# 555-Synth.net
KiCad netlist of a schematic drawn in EAGLE
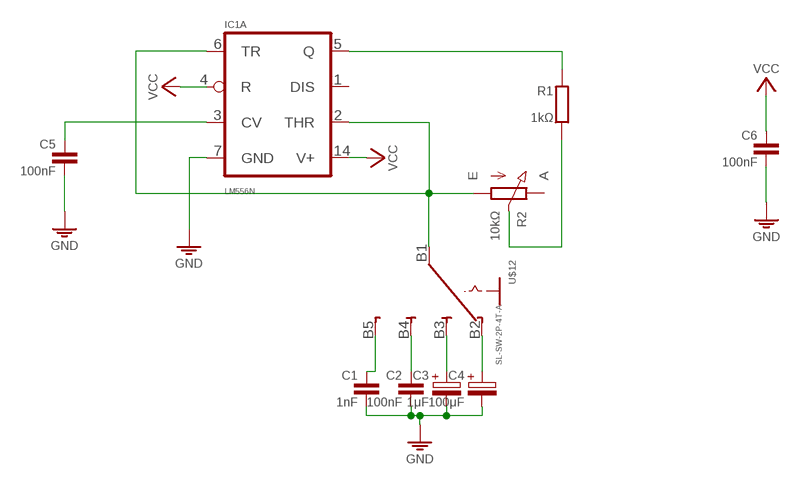
[diagram p0: schematic, sheet 1]

(export (version "E")
  (design (tool "Eeschema 10.0.6"))
  (components
    (comp (ref "C1")
      (value "1nF")
      (footprint "eagle-import:C050-020X044_V")
      (libsource (lib "eagle-import") (part "C050-020X044/V"))
    )
    (comp (ref "C2")
      (value "100nF")
      (footprint "eagle-import:C050-020X044_V")
      (libsource (lib "eagle-import") (part "C050-020X044/V"))
    )
    (comp (ref "C3")
      (value "1μF")
      (footprint "eagle-import:E2,5-5_V")
      (libsource (lib "eagle-import") (part "CPOLE2,5-5/V"))
    )
    (comp (ref "C4")
      (value "100μF")
      (footprint "eagle-import:E2,5-5_V")
      (libsource (lib "eagle-import") (part "CPOLE2,5-5/V"))
    )
    (comp (ref "C5")
      (value "100nF")
      (footprint "eagle-import:C050-020X044_V")
      (libsource (lib "eagle-import") (part "C050-020X044/V"))
    )
    (comp (ref "C6")
      (value "100nF")
      (footprint "eagle-import:C050-020X044_V")
      (libsource (lib "eagle-import") (part "C050-020X044/V"))
    )
    (comp (ref "IC1")
      (value "LM556N")
      (footprint "eagle-import:DIL14")
      (libsource (lib "eagle-import") (part "556NLM"))
    )
    (comp (ref "J1")
      (value "VCC_GNDL")
      (footprint "eagle-import:SPAD-+")
      (libsource (lib "eagle-import") (part "VCC_GNDL"))
    )
    (comp (ref "R1")
      (value "1kΩ")
      (footprint "eagle-import:0204_10-V")
      (libsource (lib "eagle-import") (part "R0204/10-V"))
    )
    (comp (ref "R2")
      (value "10kΩ")
      (footprint "eagle-import:CONN-3P")
      (libsource (lib "eagle-import") (part "POT-3P"))
    )
    (comp (ref "U$1")
      (value "SL-SW-2P-4T-A")
      (footprint "eagle-import:SLSW-2P4T-2-H")
      (libsource (lib "eagle-import") (part "SL-SW-2P-4T-A"))
    )
  )
  (nets
    (net (code "1") (name "GND") (class "Default")
      (node (ref "C1") (pin "2") (pinfunction "2_2") (pintype "passive"))
      (node (ref "C2") (pin "2") (pinfunction "2_2") (pintype "passive"))
      (node (ref "C3") (pin "-") (pinfunction "-_-") (pintype "passive"))
      (node (ref "C4") (pin "-") (pinfunction "-_-") (pintype "passive"))
      (node (ref "C5") (pin "2") (pinfunction "2_2") (pintype "passive"))
      (node (ref "C6") (pin "2") (pinfunction "2_2") (pintype "passive"))
      (node (ref "IC1") (pin "7") (pinfunction "GND_7") (pintype "power_in"))
      (node (ref "J1") (pin "1") (pinfunction "GND_1") (pintype "power_in"))
    )
    (net (code "2") (name "Net-(IC1A-CV)") (class "Default")
      (node (ref "C5") (pin "1") (pinfunction "1_1") (pintype "passive"))
      (node (ref "IC1") (pin "3") (pinfunction "CV_3") (pintype "input"))
    )
    (net (code "3") (name "Net-(IC1A-Q)") (class "Default")
      (node (ref "IC1") (pin "5") (pinfunction "Q_5") (pintype "output"))
      (node (ref "R1") (pin "1") (pinfunction "1_1") (pintype "passive"))
    )
    (net (code "4") (name "Net-(IC1A-THR)") (class "Default")
      (node (ref "IC1") (pin "2") (pinfunction "THR_2") (pintype "input"))
      (node (ref "IC1") (pin "6") (pinfunction "TR_6") (pintype "input"))
      (node (ref "R2") (pin "1") (pinfunction "A_1") (pintype "passive"))
      (node (ref "U$1") (pin "B1") (pinfunction "P_B1") (pintype "passive"))
    )
    (net (code "5") (name "Net-(R2-S)") (class "Default")
      (node (ref "R1") (pin "2") (pinfunction "2_2") (pintype "passive"))
      (node (ref "R2") (pin "2") (pinfunction "S_2") (pintype "passive"))
    )
    (net (code "6") (name "Net-(U$1B-A)") (class "Default")
      (node (ref "C4") (pin "+") (pinfunction "+_+") (pintype "passive"))
      (node (ref "U$1") (pin "B2") (pinfunction "A_B2") (pintype "passive"))
    )
    (net (code "7") (name "Net-(U$1B-B)") (class "Default")
      (node (ref "C3") (pin "+") (pinfunction "+_+") (pintype "passive"))
      (node (ref "U$1") (pin "B3") (pinfunction "B_B3") (pintype "passive"))
    )
    (net (code "8") (name "Net-(U$1B-C)") (class "Default")
      (node (ref "C2") (pin "1") (pinfunction "1_1") (pintype "passive"))
      (node (ref "U$1") (pin "B4") (pinfunction "C_B4") (pintype "passive"))
    )
    (net (code "9") (name "Net-(U$1B-D)") (class "Default")
      (node (ref "C1") (pin "1") (pinfunction "1_1") (pintype "passive"))
      (node (ref "U$1") (pin "B5") (pinfunction "D_B5") (pintype "passive"))
    )
    (net (code "10") (name "VCC") (class "Default")
      (node (ref "C6") (pin "1") (pinfunction "1_1") (pintype "passive"))
      (node (ref "IC1") (pin "14") (pinfunction "V+_14") (pintype "power_in"))
      (node (ref "IC1") (pin "4") (pinfunction "R_4") (pintype "input"))
      (node (ref "J1") (pin "2") (pinfunction "VCC_2") (pintype "power_in"))
    )
    (net (code "11") (name "unconnected-(IC1A-DIS-Pad1)") (class "Default")
      (node (ref "IC1") (pin "1") (pinfunction "DIS_1") (pintype "passive"))
    )
    (net (code "12") (name "unconnected-(R2-E-Pad3)") (class "Default")
      (node (ref "R2") (pin "3") (pinfunction "E_3") (pintype "passive"))
    )
  )
)
